# VF_Micropower.net
KiCad netlist of a schematic drawn in EAGLE
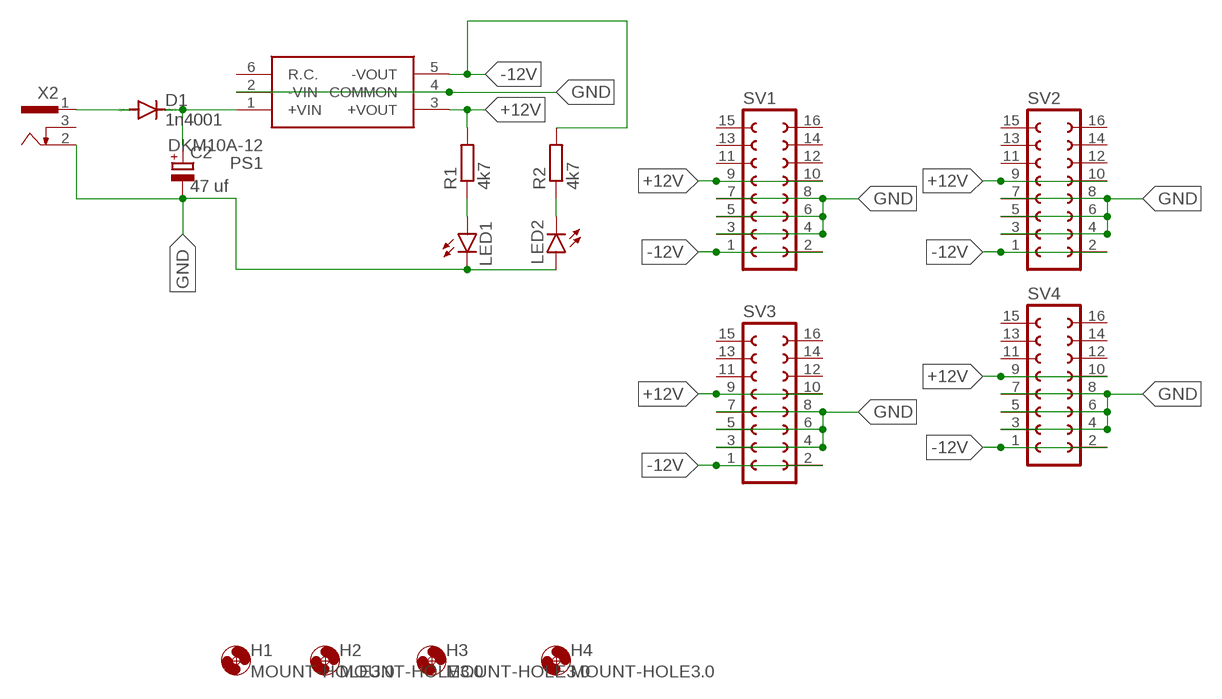
[diagram p0: schematic, sheet 1]

(export (version "E")
  (design (tool "Eeschema 10.0.6"))
  (components
    (comp (ref "C2")
      (value "47 uf")
      (footprint "eagle-import:E2,5-6E")
      (libsource (lib "eagle-import") (part "CPOL-EUE2,5-6E"))
    )
    (comp (ref "D1")
      (value "1n4001")
      (footprint "eagle-import:DO41-10")
      (libsource (lib "eagle-import") (part "1N4004"))
    )
    (comp (ref "H1")
      (value "MOUNT-HOLE3.0")
      (footprint "eagle-import:3,0")
      (libsource (lib "eagle-import") (part "MOUNT-HOLE3.0"))
    )
    (comp (ref "H2")
      (value "MOUNT-HOLE3.0")
      (footprint "eagle-import:3,0")
      (libsource (lib "eagle-import") (part "MOUNT-HOLE3.0"))
    )
    (comp (ref "H3")
      (value "MOUNT-HOLE3.0")
      (footprint "eagle-import:3,0")
      (libsource (lib "eagle-import") (part "MOUNT-HOLE3.0"))
    )
    (comp (ref "H4")
      (value "MOUNT-HOLE3.0")
      (footprint "eagle-import:3,0")
      (libsource (lib "eagle-import") (part "MOUNT-HOLE3.0"))
    )
    (comp (ref "LED1")
      (value "LED3MM")
      (footprint "eagle-import:LED3MM")
      (libsource (lib "eagle-import") (part "LED3MM"))
    )
    (comp (ref "LED2")
      (value "LED3MM")
      (footprint "eagle-import:LED3MM")
      (libsource (lib "eagle-import") (part "LED3MM"))
    )
    (comp (ref "PS1")
      (value "DKM10A-12")
      (footprint "eagle-import:SKM10B05")
      (fields (field (name "MOUSER_PART_NUMBER") "709-DKM10A-12"))
      (libsource (lib "eagle-import") (part "DKM10A-12"))
    )
    (comp (ref "R1")
      (value "4k7")
      (footprint "eagle-import:0207_10")
      (libsource (lib "eagle-import") (part "R-EU_0207/10"))
    )
    (comp (ref "R2")
      (value "4k7")
      (footprint "eagle-import:0207_10")
      (libsource (lib "eagle-import") (part "R-EU_0207/10"))
    )
    (comp (ref "SV1")
      (value "FE08-2")
      (footprint "eagle-import:FE08-2")
      (libsource (lib "eagle-import") (part "FE08-2"))
    )
    (comp (ref "SV2")
      (value "FE08-2")
      (footprint "eagle-import:FE08-2")
      (libsource (lib "eagle-import") (part "FE08-2"))
    )
    (comp (ref "SV3")
      (value "FE08-2")
      (footprint "eagle-import:FE08-2")
      (libsource (lib "eagle-import") (part "FE08-2"))
    )
    (comp (ref "SV4")
      (value "FE08-2")
      (footprint "eagle-import:FE08-2")
      (libsource (lib "eagle-import") (part "FE08-2"))
    )
    (comp (ref "X2")
      (value "SCD-014A")
      (footprint "eagle-import:SCD-014-A")
      (libsource (lib "eagle-import") (part "SCD-014A"))
    )
  )
  (nets
    (net (code "1") (name "+12V") (class "Default")
      (node (ref "PS1") (pin "3") (pinfunction "+VOUT_3") (pintype "bidirectional"))
      (node (ref "R1") (pin "2") (pinfunction "2_2") (pintype "passive"))
      (node (ref "SV1") (pin "10") (pinfunction "10_10") (pintype "passive"))
      (node (ref "SV1") (pin "9") (pinfunction "9_9") (pintype "passive"))
      (node (ref "SV2") (pin "10") (pinfunction "10_10") (pintype "passive"))
      (node (ref "SV2") (pin "9") (pinfunction "9_9") (pintype "passive"))
      (node (ref "SV3") (pin "10") (pinfunction "10_10") (pintype "passive"))
      (node (ref "SV3") (pin "9") (pinfunction "9_9") (pintype "passive"))
      (node (ref "SV4") (pin "10") (pinfunction "10_10") (pintype "passive"))
      (node (ref "SV4") (pin "9") (pinfunction "9_9") (pintype "passive"))
    )
    (net (code "2") (name "-12V") (class "Default")
      (node (ref "PS1") (pin "5") (pinfunction "-VOUT_5") (pintype "bidirectional"))
      (node (ref "R2") (pin "2") (pinfunction "2_2") (pintype "passive"))
      (node (ref "SV1") (pin "1") (pinfunction "1_1") (pintype "passive"))
      (node (ref "SV1") (pin "2") (pinfunction "2_2") (pintype "passive"))
      (node (ref "SV2") (pin "1") (pinfunction "1_1") (pintype "passive"))
      (node (ref "SV2") (pin "2") (pinfunction "2_2") (pintype "passive"))
      (node (ref "SV3") (pin "1") (pinfunction "1_1") (pintype "passive"))
      (node (ref "SV3") (pin "2") (pinfunction "2_2") (pintype "passive"))
      (node (ref "SV4") (pin "1") (pinfunction "1_1") (pintype "passive"))
      (node (ref "SV4") (pin "2") (pinfunction "2_2") (pintype "passive"))
    )
    (net (code "3") (name "GND") (class "Default")
      (node (ref "C2") (pin "-") (pinfunction "-_-") (pintype "passive"))
      (node (ref "LED1") (pin "K") (pinfunction "C_K") (pintype "passive"))
      (node (ref "LED2") (pin "A") (pinfunction "A_A") (pintype "passive"))
      (node (ref "PS1") (pin "2") (pinfunction "-VIN_2") (pintype "bidirectional"))
      (node (ref "PS1") (pin "4") (pinfunction "COMMON_4") (pintype "bidirectional"))
      (node (ref "SV1") (pin "3") (pinfunction "3_3") (pintype "passive"))
      (node (ref "SV1") (pin "4") (pinfunction "4_4") (pintype "passive"))
      (node (ref "SV1") (pin "5") (pinfunction "5_5") (pintype "passive"))
      (node (ref "SV1") (pin "6") (pinfunction "6_6") (pintype "passive"))
      (node (ref "SV1") (pin "7") (pinfunction "7_7") (pintype "passive"))
      (node (ref "SV1") (pin "8") (pinfunction "8_8") (pintype "passive"))
      (node (ref "SV2") (pin "3") (pinfunction "3_3") (pintype "passive"))
      (node (ref "SV2") (pin "4") (pinfunction "4_4") (pintype "passive"))
      (node (ref "SV2") (pin "5") (pinfunction "5_5") (pintype "passive"))
      (node (ref "SV2") (pin "6") (pinfunction "6_6") (pintype "passive"))
      (node (ref "SV2") (pin "7") (pinfunction "7_7") (pintype "passive"))
      (node (ref "SV2") (pin "8") (pinfunction "8_8") (pintype "passive"))
      (node (ref "SV3") (pin "3") (pinfunction "3_3") (pintype "passive"))
      (node (ref "SV3") (pin "4") (pinfunction "4_4") (pintype "passive"))
      (node (ref "SV3") (pin "5") (pinfunction "5_5") (pintype "passive"))
      (node (ref "SV3") (pin "6") (pinfunction "6_6") (pintype "passive"))
      (node (ref "SV3") (pin "7") (pinfunction "7_7") (pintype "passive"))
      (node (ref "SV3") (pin "8") (pinfunction "8_8") (pintype "passive"))
      (node (ref "SV4") (pin "3") (pinfunction "3_3") (pintype "passive"))
      (node (ref "SV4") (pin "4") (pinfunction "4_4") (pintype "passive"))
      (node (ref "SV4") (pin "5") (pinfunction "5_5") (pintype "passive"))
      (node (ref "SV4") (pin "6") (pinfunction "6_6") (pintype "passive"))
      (node (ref "SV4") (pin "7") (pinfunction "7_7") (pintype "passive"))
      (node (ref "SV4") (pin "8") (pinfunction "8_8") (pintype "passive"))
      (node (ref "X2") (pin "2") (pinfunction "2_2") (pintype "passive"))
    )
    (net (code "4") (name "Net-(D1-PadA)") (class "Default")
      (node (ref "D1") (pin "A") (pinfunction "A_A") (pintype "passive"))
      (node (ref "X2") (pin "1") (pinfunction "1_1") (pintype "passive"))
    )
    (net (code "5") (name "Net-(LED1-PadA)") (class "Default")
      (node (ref "LED1") (pin "A") (pinfunction "A_A") (pintype "passive"))
      (node (ref "R1") (pin "1") (pinfunction "1_1") (pintype "passive"))
    )
    (net (code "6") (name "Net-(LED2-C)") (class "Default")
      (node (ref "LED2") (pin "K") (pinfunction "C_K") (pintype "passive"))
      (node (ref "R2") (pin "1") (pinfunction "1_1") (pintype "passive"))
    )
    (net (code "7") (name "Net-(PS1-+VIN)") (class "Default")
      (node (ref "C2") (pin "+") (pinfunction "+_+") (pintype "passive"))
      (node (ref "D1") (pin "C") (pinfunction "C_C") (pintype "passive"))
      (node (ref "PS1") (pin "1") (pinfunction "+VIN_1") (pintype "bidirectional"))
    )
    (net (code "8") (name "unconnected-(PS1-R.C.-Pad6)") (class "Default")
      (node (ref "PS1") (pin "6") (pinfunction "R.C._6") (pintype "bidirectional"))
    )
    (net (code "9") (name "unconnected-(SV1-Pad11)") (class "Default")
      (node (ref "SV1") (pin "11") (pinfunction "11_11") (pintype "passive"))
    )
    (net (code "10") (name "unconnected-(SV1-Pad12)") (class "Default")
      (node (ref "SV1") (pin "12") (pinfunction "12_12") (pintype "passive"))
    )
    (net (code "11") (name "unconnected-(SV1-Pad13)") (class "Default")
      (node (ref "SV1") (pin "13") (pinfunction "13_13") (pintype "passive"))
    )
    (net (code "12") (name "unconnected-(SV1-Pad14)") (class "Default")
      (node (ref "SV1") (pin "14") (pinfunction "14_14") (pintype "passive"))
    )
    (net (code "13") (name "unconnected-(SV1-Pad15)") (class "Default")
      (node (ref "SV1") (pin "15") (pinfunction "15_15") (pintype "passive"))
    )
    (net (code "14") (name "unconnected-(SV1-Pad16)") (class "Default")
      (node (ref "SV1") (pin "16") (pinfunction "16_16") (pintype "passive"))
    )
    (net (code "15") (name "unconnected-(SV2-Pad11)") (class "Default")
      (node (ref "SV2") (pin "11") (pinfunction "11_11") (pintype "passive"))
    )
    (net (code "16") (name "unconnected-(SV2-Pad12)") (class "Default")
      (node (ref "SV2") (pin "12") (pinfunction "12_12") (pintype "passive"))
    )
    (net (code "17") (name "unconnected-(SV2-Pad13)") (class "Default")
      (node (ref "SV2") (pin "13") (pinfunction "13_13") (pintype "passive"))
    )
    (net (code "18") (name "unconnected-(SV2-Pad14)") (class "Default")
      (node (ref "SV2") (pin "14") (pinfunction "14_14") (pintype "passive"))
    )
    (net (code "19") (name "unconnected-(SV2-Pad15)") (class "Default")
      (node (ref "SV2") (pin "15") (pinfunction "15_15") (pintype "passive"))
    )
    (net (code "20") (name "unconnected-(SV2-Pad16)") (class "Default")
      (node (ref "SV2") (pin "16") (pinfunction "16_16") (pintype "passive"))
    )
    (net (code "21") (name "unconnected-(SV3-Pad11)") (class "Default")
      (node (ref "SV3") (pin "11") (pinfunction "11_11") (pintype "passive"))
    )
    (net (code "22") (name "unconnected-(SV3-Pad12)") (class "Default")
      (node (ref "SV3") (pin "12") (pinfunction "12_12") (pintype "passive"))
    )
    (net (code "23") (name "unconnected-(SV3-Pad13)") (class "Default")
      (node (ref "SV3") (pin "13") (pinfunction "13_13") (pintype "passive"))
    )
    (net (code "24") (name "unconnected-(SV3-Pad14)") (class "Default")
      (node (ref "SV3") (pin "14") (pinfunction "14_14") (pintype "passive"))
    )
    (net (code "25") (name "unconnected-(SV3-Pad15)") (class "Default")
      (node (ref "SV3") (pin "15") (pinfunction "15_15") (pintype "passive"))
    )
    (net (code "26") (name "unconnected-(SV3-Pad16)") (class "Default")
      (node (ref "SV3") (pin "16") (pinfunction "16_16") (pintype "passive"))
    )
    (net (code "27") (name "unconnected-(SV4-Pad11)") (class "Default")
      (node (ref "SV4") (pin "11") (pinfunction "11_11") (pintype "passive"))
    )
    (net (code "28") (name "unconnected-(SV4-Pad12)") (class "Default")
      (node (ref "SV4") (pin "12") (pinfunction "12_12") (pintype "passive"))
    )
    (net (code "29") (name "unconnected-(SV4-Pad13)") (class "Default")
      (node (ref "SV4") (pin "13") (pinfunction "13_13") (pintype "passive"))
    )
    (net (code "30") (name "unconnected-(SV4-Pad14)") (class "Default")
      (node (ref "SV4") (pin "14") (pinfunction "14_14") (pintype "passive"))
    )
    (net (code "31") (name "unconnected-(SV4-Pad15)") (class "Default")
      (node (ref "SV4") (pin "15") (pinfunction "15_15") (pintype "passive"))
    )
    (net (code "32") (name "unconnected-(SV4-Pad16)") (class "Default")
      (node (ref "SV4") (pin "16") (pinfunction "16_16") (pintype "passive"))
    )
    (net (code "33") (name "unconnected-(X2-Pad3)") (class "Default")
      (node (ref "X2") (pin "3") (pinfunction "3_3") (pintype "passive"))
    )
  )
)
